# Pallette_v2.net
KiCad netlist of a schematic drawn in Altium Designer
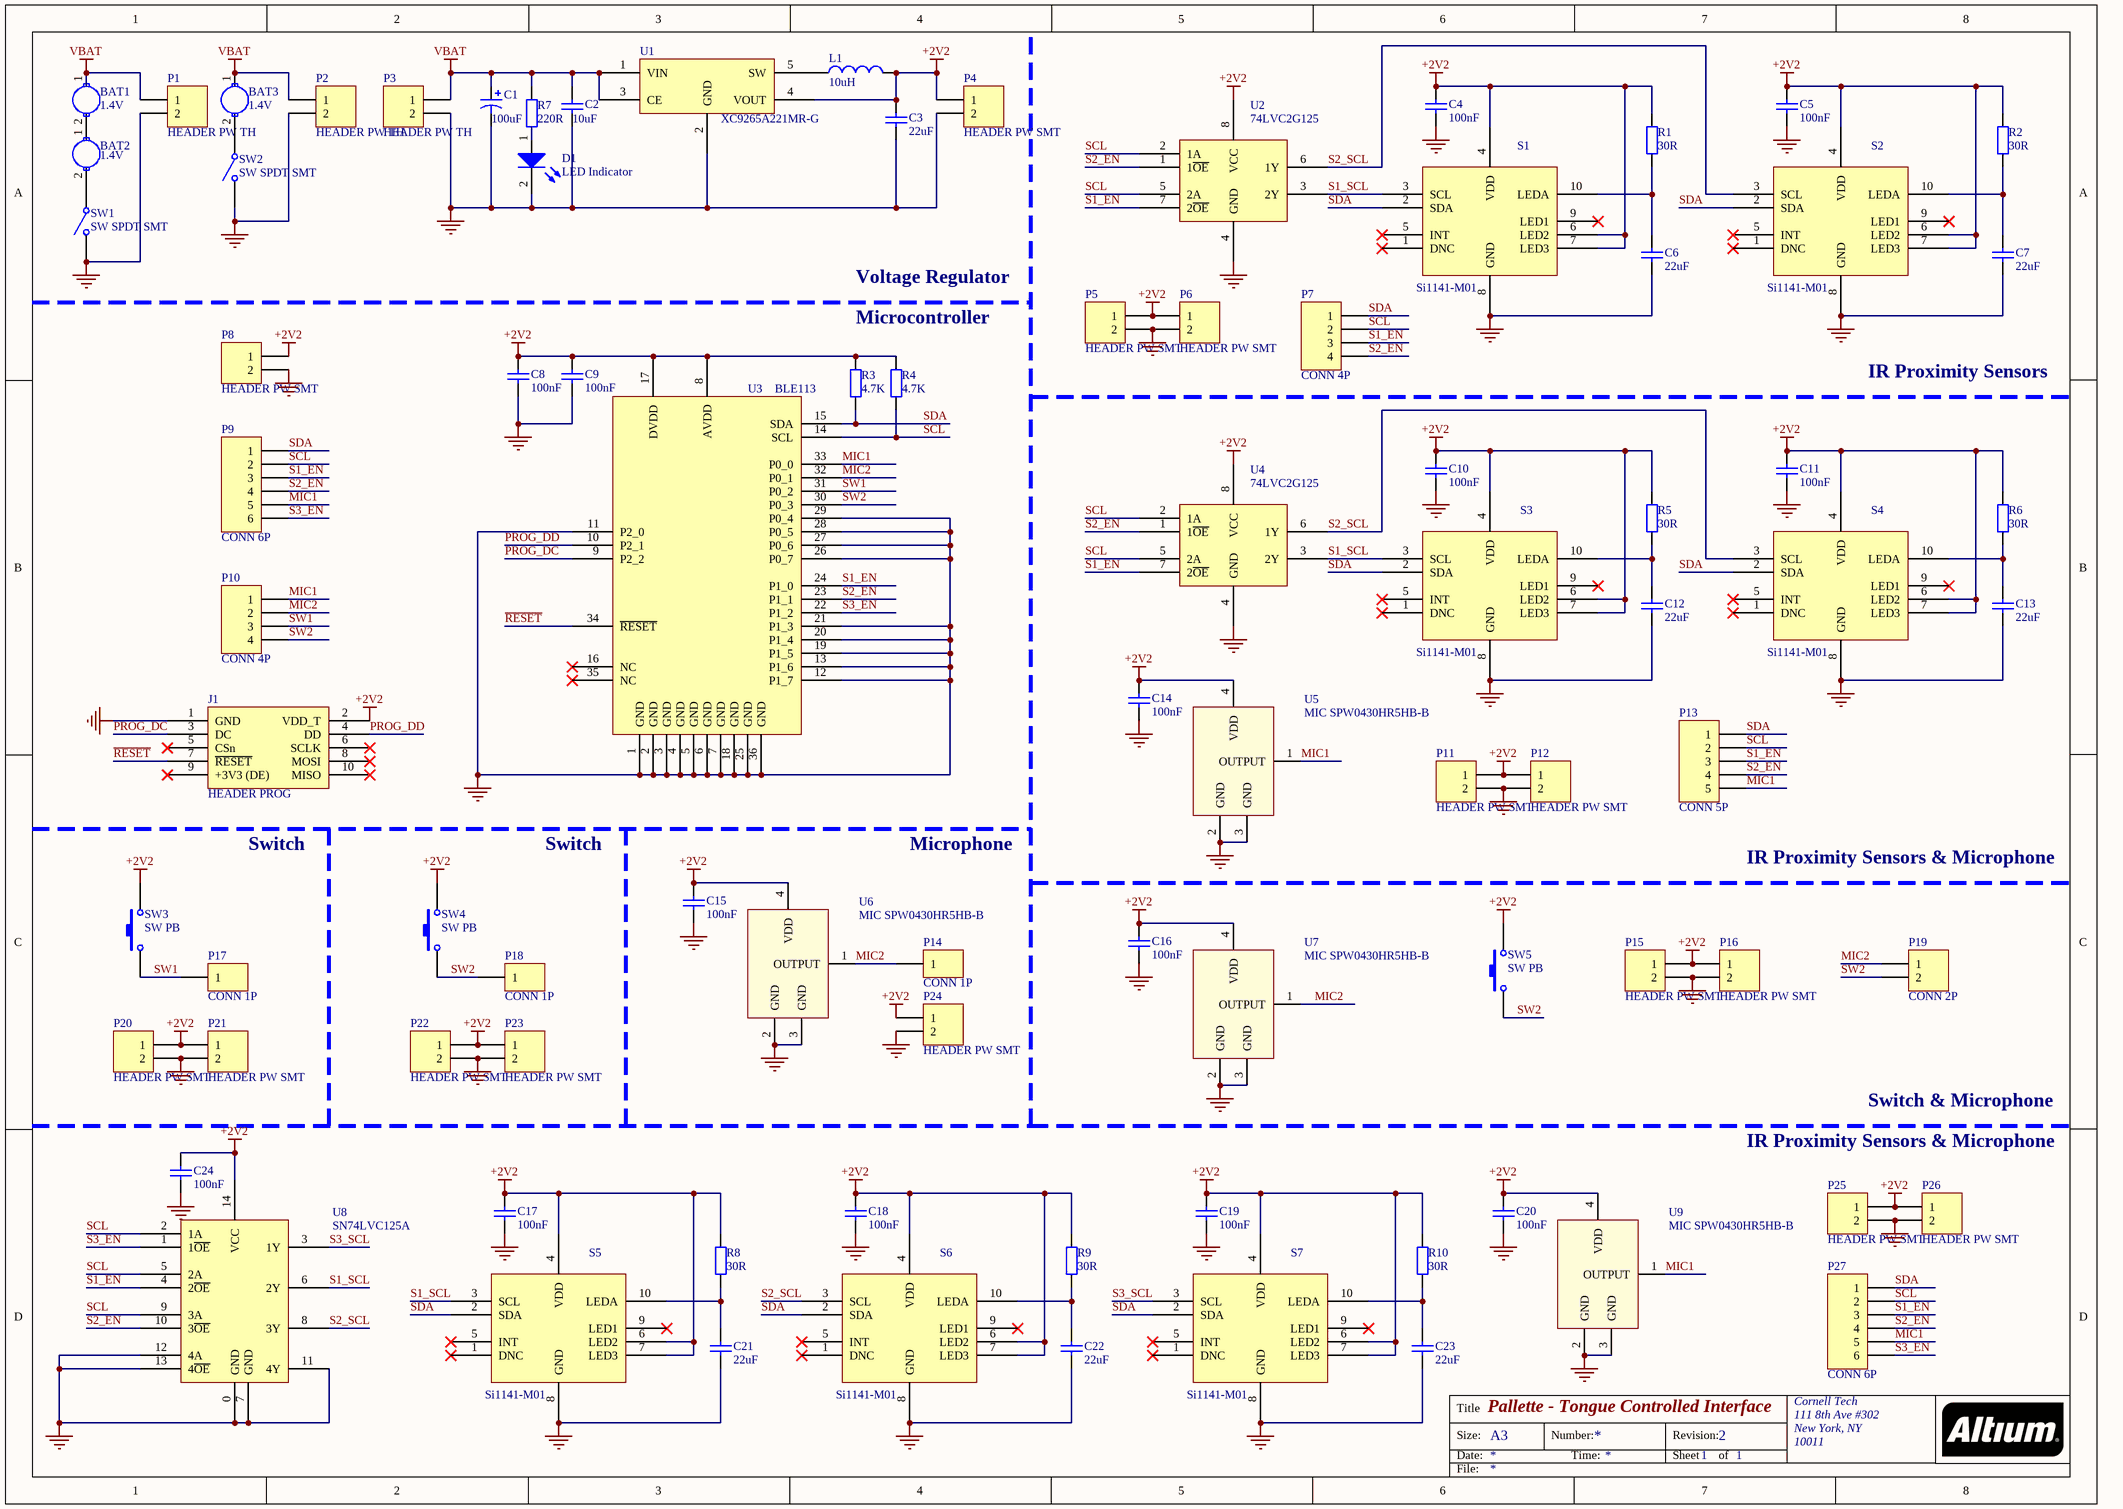
[diagram p0: Pallette v2.SchDoc]

(export (version "E")
  (design (tool "Eeschema 10.0.6"))
  (components
    (comp (ref "BAT1")
      (value "1.4V")
      (footprint "BAT RETAINER 13")
      (description "RETAINER COIN CELL SMD 7.9MM")
      (fields
        (field (name "DIGI-KEY PART NUMBER") "36-2988-ND")
        (field (name "MANUFACTURER") "Keystone Electronics")
      )
      (libsource (lib "Schlib") (part "BAT RETAINER 13"))
    )
    (comp (ref "BAT2")
      (value "1.4V")
      (footprint "BAT RETAINER 13")
      (description "RETAINER COIN CELL SMD 7.9MM")
      (fields
        (field (name "DIGI-KEY PART NUMBER") "36-2988-ND")
        (field (name "MANUFACTURER") "Keystone Electronics")
      )
      (libsource (lib "Schlib") (part "BAT RETAINER 13"))
    )
    (comp (ref "BAT3")
      (value "1.4V")
      (footprint "BAT RETAINER 13")
      (description "RETAINER COIN CELL SMD 7.9MM")
      (fields
        (field (name "DIGI-KEY PART NUMBER") "36-2988-ND")
        (field (name "MANUFACTURER") "Keystone Electronics")
      )
      (libsource (lib "Schlib") (part "BAT RETAINER 13"))
    )
    (comp (ref "C1")
      (value "100uF")
      (footprint "1411")
      (description "CAP TANT POLY 100UF 8V 1411")
      (fields
        (field (name "DIGI-KEY PART NUMBER") "P16641CT-ND")
        (field (name "MANUFACTURER") "Panasonic Electronic Components")
      )
      (libsource (lib "Schlib") (part "CAP Pol 100uF"))
    )
    (comp (ref "C2")
      (value "10uF")
      (footprint "0603")
      (description "CAP CER 10UF ±20% 10V X5R 0603")
      (fields
        (field (name "DIGI-KEY PART NUMBER") "490-12734-1-ND")
        (field (name "MANUFACTURER PART NUMBER") "GRM188R61A106MAALD")
      )
      (libsource (lib "Schlib") (part "CAP 10uF"))
    )
    (comp (ref "C3")
      (value "22uF")
      (footprint "0603")
      (description "CAP CER 22UF 6.3V X5R 0603")
      (fields
        (field (name "DIGI-KEY PART NUMBER") "490-7611-1-ND")
        (field (name "MANUFACTURER PART NUMBER") "GRM188R60J226MEA0D")
      )
      (libsource (lib "Schlib") (part "CAP 22uF"))
    )
    (comp (ref "C4")
      (value "100nF")
      (footprint "0402")
      (description "CAP CER 0.1UF 10V X5R 0402")
      (fields (field (name "DIGI-KEY PART NUMBER") "490-1318-1-ND") (field (name "MANUFACTURER") "Murata"))
      (libsource (lib "Schlib") (part "CAP 100nF"))
    )
    (comp (ref "C5")
      (value "100nF")
      (footprint "0402")
      (description "CAP CER 0.1UF 10V X5R 0402")
      (fields (field (name "DIGI-KEY PART NUMBER") "490-1318-1-ND") (field (name "MANUFACTURER") "Murata"))
      (libsource (lib "Schlib") (part "CAP 100nF"))
    )
    (comp (ref "C6")
      (value "22uF")
      (footprint "0603")
      (description "CAP CER 22UF 6.3V X5R 0603")
      (fields
        (field (name "DIGI-KEY PART NUMBER") "490-7611-1-ND")
        (field (name "MANUFACTURER PART NUMBER") "GRM188R60J226MEA0D")
      )
      (libsource (lib "Schlib") (part "CAP 22uF"))
    )
    (comp (ref "C7")
      (value "22uF")
      (footprint "0603")
      (description "CAP CER 22UF 6.3V X5R 0603")
      (fields
        (field (name "DIGI-KEY PART NUMBER") "490-7611-1-ND")
        (field (name "MANUFACTURER PART NUMBER") "GRM188R60J226MEA0D")
      )
      (libsource (lib "Schlib") (part "CAP 22uF"))
    )
    (comp (ref "C8")
      (value "100nF")
      (footprint "0402")
      (description "CAP CER 0.1UF 10V X5R 0402")
      (fields (field (name "DIGI-KEY PART NUMBER") "490-1318-1-ND") (field (name "MANUFACTURER") "Murata"))
      (libsource (lib "Schlib") (part "CAP 100nF"))
    )
    (comp (ref "C9")
      (value "100nF")
      (footprint "0402")
      (description "CAP CER 0.1UF 10V X5R 0402")
      (fields (field (name "DIGI-KEY PART NUMBER") "490-1318-1-ND") (field (name "MANUFACTURER") "Murata"))
      (libsource (lib "Schlib") (part "CAP 100nF"))
    )
    (comp (ref "C10")
      (value "100nF")
      (footprint "0402")
      (description "CAP CER 0.1UF 10V X5R 0402")
      (fields (field (name "DIGI-KEY PART NUMBER") "490-1318-1-ND") (field (name "MANUFACTURER") "Murata"))
      (libsource (lib "Schlib") (part "CAP 100nF"))
    )
    (comp (ref "C11")
      (value "100nF")
      (footprint "0402")
      (description "CAP CER 0.1UF 10V X5R 0402")
      (fields (field (name "DIGI-KEY PART NUMBER") "490-1318-1-ND") (field (name "MANUFACTURER") "Murata"))
      (libsource (lib "Schlib") (part "CAP 100nF"))
    )
    (comp (ref "C12")
      (value "22uF")
      (footprint "0603")
      (description "CAP CER 22UF 6.3V X5R 0603")
      (fields
        (field (name "DIGI-KEY PART NUMBER") "490-7611-1-ND")
        (field (name "MANUFACTURER PART NUMBER") "GRM188R60J226MEA0D")
      )
      (libsource (lib "Schlib") (part "CAP 22uF"))
    )
    (comp (ref "C13")
      (value "22uF")
      (footprint "0603")
      (description "CAP CER 22UF 6.3V X5R 0603")
      (fields
        (field (name "DIGI-KEY PART NUMBER") "490-7611-1-ND")
        (field (name "MANUFACTURER PART NUMBER") "GRM188R60J226MEA0D")
      )
      (libsource (lib "Schlib") (part "CAP 22uF"))
    )
    (comp (ref "C14")
      (value "100nF")
      (footprint "0402")
      (description "CAP CER 0.1UF 10V X5R 0402")
      (fields (field (name "DIGI-KEY PART NUMBER") "490-1318-1-ND") (field (name "MANUFACTURER") "Murata"))
      (libsource (lib "Schlib") (part "CAP 100nF"))
    )
    (comp (ref "C15")
      (value "100nF")
      (footprint "0402")
      (description "CAP CER 0.1UF 10V X5R 0402")
      (fields (field (name "DIGI-KEY PART NUMBER") "490-1318-1-ND") (field (name "MANUFACTURER") "Murata"))
      (libsource (lib "Schlib") (part "CAP 100nF"))
    )
    (comp (ref "C16")
      (value "100nF")
      (footprint "0402")
      (description "CAP CER 0.1UF 10V X5R 0402")
      (fields (field (name "DIGI-KEY PART NUMBER") "490-1318-1-ND") (field (name "MANUFACTURER") "Murata"))
      (libsource (lib "Schlib") (part "CAP 100nF"))
    )
    (comp (ref "C17")
      (value "100nF")
      (footprint "0402")
      (description "CAP CER 0.1UF 10V X5R 0402")
      (fields (field (name "DIGI-KEY PART NUMBER") "490-1318-1-ND") (field (name "MANUFACTURER") "Murata"))
      (libsource (lib "Schlib") (part "CAP 100nF"))
    )
    (comp (ref "C18")
      (value "100nF")
      (footprint "0402")
      (description "CAP CER 0.1UF 10V X5R 0402")
      (fields (field (name "DIGI-KEY PART NUMBER") "490-1318-1-ND") (field (name "MANUFACTURER") "Murata"))
      (libsource (lib "Schlib") (part "CAP 100nF"))
    )
    (comp (ref "C19")
      (value "100nF")
      (footprint "0402")
      (description "CAP CER 0.1UF 10V X5R 0402")
      (fields (field (name "DIGI-KEY PART NUMBER") "490-1318-1-ND") (field (name "MANUFACTURER") "Murata"))
      (libsource (lib "Schlib") (part "CAP 100nF"))
    )
    (comp (ref "C20")
      (value "100nF")
      (footprint "0402")
      (description "CAP CER 0.1UF 10V X5R 0402")
      (fields (field (name "DIGI-KEY PART NUMBER") "490-1318-1-ND") (field (name "MANUFACTURER") "Murata"))
      (libsource (lib "Schlib") (part "CAP 100nF"))
    )
    (comp (ref "C21")
      (value "22uF")
      (footprint "0603")
      (description "CAP CER 22UF 6.3V X5R 0603")
      (fields
        (field (name "DIGI-KEY PART NUMBER") "490-7611-1-ND")
        (field (name "MANUFACTURER PART NUMBER") "GRM188R60J226MEA0D")
      )
      (libsource (lib "Schlib") (part "CAP 22uF"))
    )
    (comp (ref "C22")
      (value "22uF")
      (footprint "0603")
      (description "CAP CER 22UF 6.3V X5R 0603")
      (fields
        (field (name "DIGI-KEY PART NUMBER") "490-7611-1-ND")
        (field (name "MANUFACTURER PART NUMBER") "GRM188R60J226MEA0D")
      )
      (libsource (lib "Schlib") (part "CAP 22uF"))
    )
    (comp (ref "C23")
      (value "22uF")
      (footprint "0603")
      (description "CAP CER 22UF 6.3V X5R 0603")
      (fields
        (field (name "DIGI-KEY PART NUMBER") "490-7611-1-ND")
        (field (name "MANUFACTURER PART NUMBER") "GRM188R60J226MEA0D")
      )
      (libsource (lib "Schlib") (part "CAP 22uF"))
    )
    (comp (ref "C24")
      (value "100nF")
      (footprint "0402")
      (description "CAP CER 0.1UF 10V X5R 0402")
      (fields (field (name "DIGI-KEY PART NUMBER") "490-1318-1-ND") (field (name "MANUFACTURER") "Murata"))
      (libsource (lib "Schlib") (part "CAP 100nF"))
    )
    (comp (ref "D1")
      (value "LED Indicator")
      (footprint "LED")
      (description "LED Red 630nm 2.2V Diffused White Lens 0603")
      (fields
        (field (name "DIGIKEY PART NUMBER") "SML-D12V1WT86CT-ND")
        (field (name "MANUFACTURER PART NUMBER") "SML-D12V1WT86")
      )
      (libsource (lib "Schlib") (part "LED Indicator"))
    )
    (comp (ref "J1")
      (value "HEADER PROG")
      (footprint "TC2050-IDC-NL")
      (description "PADS PROGRAMMING")
      (libsource (lib "Schlib") (part "HEADER PROG"))
    )
    (comp (ref "L1")
      (value "10uH")
      (footprint "0805")
      (description "FIXED IND 10UH 500MA 320 MOHM")
      (fields
        (field (name "DIGI-KEY PART NUMBER") "535-12791-1-ND")
        (field (name "MANUFACTURER") "Abracon LLC")
      )
      (libsource (lib "Schlib") (part "IND 10uH"))
    )
    (comp (ref "P1")
      (value "HEADER PW TH")
      (footprint "PORT PW TH 2P")
      (description "PADS POWER")
      (fields (field (name "PUBLISHER") "Altium Limited"))
      (libsource (lib "Schlib") (part "HEADER PW TH"))
    )
    (comp (ref "P2")
      (value "HEADER PW TH")
      (footprint "PORT PW TH 2P")
      (description "PADS POWER")
      (fields (field (name "PUBLISHER") "Altium Limited"))
      (libsource (lib "Schlib") (part "HEADER PW TH"))
    )
    (comp (ref "P3")
      (value "HEADER PW TH")
      (footprint "PORT PW TH 2P")
      (description "PADS POWER")
      (fields (field (name "PUBLISHER") "Altium Limited"))
      (libsource (lib "") (part "HEADER PW TH_1"))
    )
    (comp (ref "P4")
      (value "HEADER PW SMT")
      (footprint "PORT PW SMT 2P")
      (description "Connection Port")
      (fields (field (name "PUBLISHER") "Altium Limited"))
      (libsource (lib "Schlib") (part "HEADER PW SMT"))
    )
    (comp (ref "P5")
      (value "HEADER PW SMT")
      (footprint "PORT PW SMT 2P")
      (description "Connection Port")
      (fields (field (name "PUBLISHER") "Altium Limited"))
      (libsource (lib "") (part "HEADER PW SMT_1"))
    )
    (comp (ref "P6")
      (value "HEADER PW SMT")
      (footprint "PORT PW SMT 2P")
      (description "Connection Port")
      (fields (field (name "PUBLISHER") "Altium Limited"))
      (libsource (lib "Schlib") (part "HEADER PW SMT"))
    )
    (comp (ref "P7")
      (value "CONN 4P")
      (footprint "PORT CONN 4P")
      (description "Connection Port")
      (fields (field (name "PUBLISHER") "Altium Limited"))
      (libsource (lib "Schlib") (part "HEADER CONN 4P"))
    )
    (comp (ref "P8")
      (value "HEADER PW SMT")
      (footprint "PORT PW SMT 2P")
      (description "Connection Port")
      (fields (field (name "PUBLISHER") "Altium Limited"))
      (libsource (lib "") (part "HEADER PW SMT_1"))
    )
    (comp (ref "P9")
      (value "CONN 6P")
      (footprint "PORT CONN 6P")
      (description "Connection Port")
      (fields (field (name "PUBLISHER") "Altium Limited"))
      (libsource (lib "Schlib") (part "HEADER CONN 6P"))
    )
    (comp (ref "P10")
      (value "CONN 4P")
      (footprint "PORT CONN 4P")
      (description "Connection Port")
      (fields (field (name "PUBLISHER") "Altium Limited"))
      (libsource (lib "Schlib") (part "HEADER CONN 4P"))
    )
    (comp (ref "P11")
      (value "HEADER PW SMT")
      (footprint "PORT PW SMT 2P")
      (description "Connection Port")
      (fields (field (name "PUBLISHER") "Altium Limited"))
      (libsource (lib "") (part "HEADER PW SMT_1"))
    )
    (comp (ref "P12")
      (value "HEADER PW SMT")
      (footprint "PORT PW SMT 2P")
      (description "Connection Port")
      (fields (field (name "PUBLISHER") "Altium Limited"))
      (libsource (lib "Schlib") (part "HEADER PW SMT"))
    )
    (comp (ref "P13")
      (value "CONN 5P")
      (footprint "PORT CONN 5P")
      (description "Connection Port")
      (libsource (lib "Schlib") (part "HEADER CONN 5P"))
    )
    (comp (ref "P14")
      (value "CONN 1P")
      (footprint "PORT CONN 1P")
      (description "Connection Port")
      (libsource (lib "Schlib") (part "HEADER CONN 1P"))
    )
    (comp (ref "P15")
      (value "HEADER PW SMT")
      (footprint "PORT PW SMT 2P")
      (description "Connection Port")
      (fields (field (name "PUBLISHER") "Altium Limited"))
      (libsource (lib "") (part "HEADER PW SMT_1"))
    )
    (comp (ref "P16")
      (value "HEADER PW SMT")
      (footprint "PORT PW SMT 2P")
      (description "Connection Port")
      (fields (field (name "PUBLISHER") "Altium Limited"))
      (libsource (lib "Schlib") (part "HEADER PW SMT"))
    )
    (comp (ref "P17")
      (value "CONN 1P")
      (footprint "PORT CONN 1P")
      (description "Connection Port")
      (libsource (lib "Schlib") (part "HEADER CONN 1P"))
    )
    (comp (ref "P18")
      (value "CONN 1P")
      (footprint "PORT CONN 1P")
      (description "Connection Port")
      (libsource (lib "Schlib") (part "HEADER CONN 1P"))
    )
    (comp (ref "P19")
      (value "CONN 2P")
      (footprint "PORT CONN 2P")
      (description "Connection Port")
      (fields (field (name "PUBLISHER") "Altium Limited"))
      (libsource (lib "Schlib") (part "HEADER CONN 2P"))
    )
    (comp (ref "P20")
      (value "HEADER PW SMT")
      (footprint "PORT PW SMT 2P")
      (description "Connection Port")
      (fields (field (name "PUBLISHER") "Altium Limited"))
      (libsource (lib "") (part "HEADER PW SMT_1"))
    )
    (comp (ref "P21")
      (value "HEADER PW SMT")
      (footprint "PORT PW SMT 2P")
      (description "Connection Port")
      (fields (field (name "PUBLISHER") "Altium Limited"))
      (libsource (lib "Schlib") (part "HEADER PW SMT"))
    )
    (comp (ref "P22")
      (value "HEADER PW SMT")
      (footprint "PORT PW SMT 2P")
      (description "Connection Port")
      (fields (field (name "PUBLISHER") "Altium Limited"))
      (libsource (lib "") (part "HEADER PW SMT_1"))
    )
    (comp (ref "P23")
      (value "HEADER PW SMT")
      (footprint "PORT PW SMT 2P")
      (description "Connection Port")
      (fields (field (name "PUBLISHER") "Altium Limited"))
      (libsource (lib "Schlib") (part "HEADER PW SMT"))
    )
    (comp (ref "P24")
      (value "HEADER PW SMT")
      (footprint "PORT PW SMT 2P")
      (description "Connection Port")
      (fields (field (name "PUBLISHER") "Altium Limited"))
      (libsource (lib "Schlib") (part "HEADER PW SMT"))
    )
    (comp (ref "P25")
      (value "HEADER PW SMT")
      (footprint "PORT PW SMT 2P")
      (description "Connection Port")
      (fields (field (name "PUBLISHER") "Altium Limited"))
      (libsource (lib "") (part "HEADER PW SMT_1"))
    )
    (comp (ref "P26")
      (value "HEADER PW SMT")
      (footprint "PORT PW SMT 2P")
      (description "Connection Port")
      (fields (field (name "PUBLISHER") "Altium Limited"))
      (libsource (lib "Schlib") (part "HEADER PW SMT"))
    )
    (comp (ref "P27")
      (value "CONN 6P")
      (footprint "PORT CONN 6P")
      (description "Connection Port")
      (fields (field (name "PUBLISHER") "Altium Limited"))
      (libsource (lib "Schlib") (part "HEADER CONN 6P"))
    )
    (comp (ref "R1")
      (value "30R")
      (footprint "0402")
      (description "RES SMD 30 OHM 1% 1/16W 0402")
      (fields (field (name "DIGI-KEY PART NUMBER") "311-30LRCT-ND") (field (name "MANUFACTURER") "Yageo"))
      (libsource (lib "Schlib") (part "RES 30R"))
    )
    (comp (ref "R2")
      (value "30R")
      (footprint "0402")
      (description "RES SMD 30 OHM 1% 1/16W 0402")
      (fields (field (name "DIGI-KEY PART NUMBER") "311-30LRCT-ND") (field (name "MANUFACTURER") "Yageo"))
      (libsource (lib "Schlib") (part "RES 30R"))
    )
    (comp (ref "R3")
      (value "4.7K")
      (footprint "0402")
      (description "RES SMD 4.7K OHM 1% 1/16W 0402")
      (fields (field (name "DIGI-KEY PART NUMBER") "311-4.7KLRCT-ND") (field (name "MANUFACTURER") "Yageo"))
      (libsource (lib "Schlib") (part "RES 4.7K"))
    )
    (comp (ref "R4")
      (value "4.7K")
      (footprint "0402")
      (description "RES SMD 4.7K OHM 1% 1/16W 0402")
      (fields (field (name "DIGI-KEY PART NUMBER") "311-4.7KLRCT-ND") (field (name "MANUFACTURER") "Yageo"))
      (libsource (lib "Schlib") (part "RES 4.7K"))
    )
    (comp (ref "R5")
      (value "30R")
      (footprint "0402")
      (description "RES SMD 30 OHM 1% 1/16W 0402")
      (fields (field (name "DIGI-KEY PART NUMBER") "311-30LRCT-ND") (field (name "MANUFACTURER") "Yageo"))
      (libsource (lib "Schlib") (part "RES 30R"))
    )
    (comp (ref "R6")
      (value "30R")
      (footprint "0402")
      (description "RES SMD 30 OHM 1% 1/16W 0402")
      (fields (field (name "DIGI-KEY PART NUMBER") "311-30LRCT-ND") (field (name "MANUFACTURER") "Yageo"))
      (libsource (lib "Schlib") (part "RES 30R"))
    )
    (comp (ref "R7")
      (value "220R")
      (footprint "0603")
      (description "RES SMD 220 OHM 1% 1/10W 0603")
      (fields (field (name "DIGI-KEY PART NUMBER") "P220HCT-ND") (field (name "MANUFACTURER") "Panasonic"))
      (libsource (lib "Schlib") (part "RES 220R"))
    )
    (comp (ref "R8")
      (value "30R")
      (footprint "0402")
      (description "RES SMD 30 OHM 1% 1/16W 0402")
      (fields (field (name "DIGI-KEY PART NUMBER") "311-30LRCT-ND") (field (name "MANUFACTURER") "Yageo"))
      (libsource (lib "Schlib") (part "RES 30R"))
    )
    (comp (ref "R9")
      (value "30R")
      (footprint "0402")
      (description "RES SMD 30 OHM 1% 1/16W 0402")
      (fields (field (name "DIGI-KEY PART NUMBER") "311-30LRCT-ND") (field (name "MANUFACTURER") "Yageo"))
      (libsource (lib "Schlib") (part "RES 30R"))
    )
    (comp (ref "R10")
      (value "30R")
      (footprint "0402")
      (description "RES SMD 30 OHM 1% 1/16W 0402")
      (fields (field (name "DIGI-KEY PART NUMBER") "311-30LRCT-ND") (field (name "MANUFACTURER") "Yageo"))
      (libsource (lib "Schlib") (part "RES 30R"))
    )
    (comp (ref "S1")
      (value "Si1141-M01")
      (footprint "SI1141-M01")
      (description "SENS IR PROXIMITY AMB LT 10QFN")
      (fields
        (field (name "DIGI-KEY PART NUMBER") "336-3260-1-ND")
        (field (name "MANUFACTURER") "Silicon Labs")
      )
      (libsource (lib "Schlib") (part "Si1141-M01"))
    )
    (comp (ref "S2")
      (value "Si1141-M01")
      (footprint "SI1141-M01")
      (description "SENS IR PROXIMITY AMB LT 10QFN")
      (fields
        (field (name "DIGI-KEY PART NUMBER") "336-3260-1-ND")
        (field (name "MANUFACTURER") "Silicon Labs")
      )
      (libsource (lib "Schlib") (part "Si1141-M01"))
    )
    (comp (ref "S3")
      (value "Si1141-M01")
      (footprint "SI1141-M01")
      (description "SENS IR PROXIMITY AMB LT 10QFN")
      (fields
        (field (name "DIGI-KEY PART NUMBER") "336-3260-1-ND")
        (field (name "MANUFACTURER") "Silicon Labs")
      )
      (libsource (lib "Schlib") (part "Si1141-M01"))
    )
    (comp (ref "S4")
      (value "Si1141-M01")
      (footprint "SI1141-M01")
      (description "SENS IR PROXIMITY AMB LT 10QFN")
      (fields
        (field (name "DIGI-KEY PART NUMBER") "336-3260-1-ND")
        (field (name "MANUFACTURER") "Silicon Labs")
      )
      (libsource (lib "Schlib") (part "Si1141-M01"))
    )
    (comp (ref "S5")
      (value "Si1141-M01")
      (footprint "SI1141-M01")
      (description "SENS IR PROXIMITY AMB LT 10QFN")
      (fields
        (field (name "DIGI-KEY PART NUMBER") "336-3260-1-ND")
        (field (name "MANUFACTURER") "Silicon Labs")
      )
      (libsource (lib "Schlib") (part "Si1141-M01"))
    )
    (comp (ref "S6")
      (value "Si1141-M01")
      (footprint "SI1141-M01")
      (description "SENS IR PROXIMITY AMB LT 10QFN")
      (fields
        (field (name "DIGI-KEY PART NUMBER") "336-3260-1-ND")
        (field (name "MANUFACTURER") "Silicon Labs")
      )
      (libsource (lib "Schlib") (part "Si1141-M01"))
    )
    (comp (ref "S7")
      (value "Si1141-M01")
      (footprint "SI1141-M01")
      (description "SENS IR PROXIMITY AMB LT 10QFN")
      (fields
        (field (name "DIGI-KEY PART NUMBER") "336-3260-1-ND")
        (field (name "MANUFACTURER") "Silicon Labs")
      )
      (libsource (lib "Schlib") (part "Si1141-M01"))
    )
    (comp (ref "SW1")
      (value "SW SPDT SMT")
      (footprint "SW SPDT SMT")
      (description "SW Single-Pole Double-Throw SMT Right-Angle")
      (fields
        (field (name "DIGIKEY PART NUMBER") "401-2000-ND")
        (field (name "MANUFACTURER") "C&K Components")
      )
      (libsource (lib "Schlib") (part "SW SPDT SMT"))
    )
    (comp (ref "SW2")
      (value "SW SPDT SMT")
      (footprint "SW SPDT SMT")
      (description "SW Single-Pole Double-Throw SMT Right-Angle")
      (fields
        (field (name "DIGIKEY PART NUMBER") "401-2000-ND")
        (field (name "MANUFACTURER") "C&K Components")
      )
      (libsource (lib "Schlib") (part "SW SPDT SMT"))
    )
    (comp (ref "SW3")
      (value "SW PB")
      (footprint "SW PB")
      (description "Switch Button")
      (libsource (lib "Schlib") (part "SW PB"))
    )
    (comp (ref "SW4")
      (value "SW PB")
      (footprint "SW PB")
      (description "Switch Button")
      (libsource (lib "Schlib") (part "SW PB"))
    )
    (comp (ref "SW5")
      (value "SW PB")
      (footprint "SW PB")
      (description "Switch Button")
      (libsource (lib "Schlib") (part "SW PB"))
    )
    (comp (ref "U1")
      (value "XC9265A221MR-G")
      (footprint "SOT-25")
      (description "IC REG BUCK 2.2V 0.2A SYNC SOT25")
      (fields
        (field (name "DIGI-KEY PART NUMBER") "893-1305-1-ND")
        (field (name "MANUFACTURER") "Torex Semiconductor Ltd")
      )
      (libsource (lib "Schlib") (part "VR XC9265A221MR-G"))
    )
    (comp (ref "U2")
      (value "74LVC2G125")
      (footprint "VSSOP8")
      (description "IC BUS BUFF DVR TRI-ST DL 8VSSOP")
      (fields
        (field (name "MANUFACTURER") "NXP Semiconductors")
        (field (name "MANUFACTURER PART NUMBER") "74LVC2G125DC,125")
      )
      (libsource (lib "Schlib") (part "BUFF 74LVC2G125"))
    )
    (comp (ref "U3")
      (value "BLE113")
      (footprint "BLE113-A")
      (description "MODULE BT 4.0 BLE113 OTA")
      (fields
        (field (name "MANUFACTURER") "Silicon Labs")
        (field (name "MANUFACTURER PART NUMBER") "BLE113-A-M256K")
      )
      (libsource (lib "Schlib") (part "uC BLE113"))
    )
    (comp (ref "U4")
      (value "74LVC2G125")
      (footprint "VSSOP8")
      (description "IC BUS BUFF DVR TRI-ST DL 8VSSOP")
      (fields
        (field (name "MANUFACTURER") "NXP Semiconductors")
        (field (name "MANUFACTURER PART NUMBER") "74LVC2G125DC,125")
      )
      (libsource (lib "Schlib") (part "BUFF 74LVC2G125"))
    )
    (comp (ref "U5")
      (value "MIC SPW0430HR5HB-B")
      (footprint "MIC-4P")
      (description "MIC MEMS ANALOG OMNI")
      (fields (field (name "DIGI-KEY PART NUMBER") "423-1215-1-ND") (field (name "MANUFACTURER") "Knowles"))
      (libsource (lib "Schlib") (part "MIC SPW0430HR5HB-B"))
    )
    (comp (ref "U6")
      (value "MIC SPW0430HR5HB-B")
      (footprint "MIC-4P")
      (description "MIC MEMS ANALOG OMNI")
      (fields (field (name "DIGI-KEY PART NUMBER") "423-1215-1-ND") (field (name "MANUFACTURER") "Knowles"))
      (libsource (lib "Schlib") (part "MIC SPW0430HR5HB-B"))
    )
    (comp (ref "U7")
      (value "MIC SPW0430HR5HB-B")
      (footprint "MIC-4P")
      (description "MIC MEMS ANALOG OMNI")
      (fields (field (name "DIGI-KEY PART NUMBER") "423-1215-1-ND") (field (name "MANUFACTURER") "Knowles"))
      (libsource (lib "Schlib") (part "MIC SPW0430HR5HB-B"))
    )
    (comp (ref "U8")
      (value "SN74LVC125A")
      (footprint "VQFN14")
      (description "IC BUS BUFF TRI-ST QD 14VQFN")
      (fields
        (field (name "MANUFACTURER") "Texas Instruments")
        (field (name "MANUFACTURER PART NUMBER") "SN74LVC125ARGYR")
      )
      (libsource (lib "Schlib") (part "BUFF SN74LVC125A"))
    )
    (comp (ref "U9")
      (value "MIC SPW0430HR5HB-B")
      (footprint "MIC-4P")
      (description "MIC MEMS ANALOG OMNI")
      (fields (field (name "DIGI-KEY PART NUMBER") "423-1215-1-ND") (field (name "MANUFACTURER") "Knowles"))
      (libsource (lib "Schlib") (part "MIC SPW0430HR5HB-B"))
    )
  )
  (nets
    (net (code "1") (name "+2V2") (class "Default")
      (node (ref "C10") (pin "2") (pinfunction "2_2") (pintype "passive"))
      (node (ref "C11") (pin "2") (pinfunction "2_2") (pintype "passive"))
      (node (ref "C14") (pin "1") (pinfunction "1_1") (pintype "passive"))
      (node (ref "C15") (pin "1") (pinfunction "1_1") (pintype "passive"))
      (node (ref "C16") (pin "1") (pinfunction "1_1") (pintype "passive"))
      (node (ref "C17") (pin "2") (pinfunction "2_2") (pintype "passive"))
      (node (ref "C18") (pin "2") (pinfunction "2_2") (pintype "passive"))
      (node (ref "C19") (pin "2") (pinfunction "2_2") (pintype "passive"))
      (node (ref "C20") (pin "1") (pinfunction "1_1") (pintype "passive"))
      (node (ref "C24") (pin "2") (pinfunction "2_2") (pintype "passive"))
      (node (ref "C3") (pin "2") (pinfunction "2_2") (pintype "passive"))
      (node (ref "C4") (pin "2") (pinfunction "2_2") (pintype "passive"))
      (node (ref "C5") (pin "2") (pinfunction "2_2") (pintype "passive"))
      (node (ref "C8") (pin "2") (pinfunction "2_2") (pintype "passive"))
      (node (ref "C9") (pin "2") (pinfunction "2_2") (pintype "passive"))
      (node (ref "J1") (pin "2") (pinfunction "VDD_T_2") (pintype "passive"))
      (node (ref "L1") (pin "2") (pinfunction "2_2") (pintype "passive"))
      (node (ref "P11") (pin "1") (pinfunction "1_1") (pintype "passive"))
      (node (ref "P12") (pin "1") (pinfunction "1_1") (pintype "passive"))
      (node (ref "P15") (pin "1") (pinfunction "1_1") (pintype "passive"))
      (node (ref "P16") (pin "1") (pinfunction "1_1") (pintype "passive"))
      (node (ref "P20") (pin "1") (pinfunction "1_1") (pintype "passive"))
      (node (ref "P21") (pin "1") (pinfunction "1_1") (pintype "passive"))
      (node (ref "P22") (pin "1") (pinfunction "1_1") (pintype "passive"))
      (node (ref "P23") (pin "1") (pinfunction "1_1") (pintype "passive"))
      (node (ref "P24") (pin "1") (pinfunction "1_1") (pintype "passive"))
      (node (ref "P25") (pin "1") (pinfunction "1_1") (pintype "passive"))
      (node (ref "P26") (pin "1") (pinfunction "1_1") (pintype "passive"))
      (node (ref "P4") (pin "1") (pinfunction "1_1") (pintype "passive"))
      (node (ref "P5") (pin "1") (pinfunction "1_1") (pintype "passive"))
      (node (ref "P6") (pin "1") (pinfunction "1_1") (pintype "passive"))
      (node (ref "P8") (pin "1") (pinfunction "1_1") (pintype "passive"))
      (node (ref "R1") (pin "2") (pinfunction "2_2") (pintype "passive"))
      (node (ref "R10") (pin "2") (pinfunction "2_2") (pintype "passive"))
      (node (ref "R2") (pin "2") (pinfunction "2_2") (pintype "passive"))
      (node (ref "R3") (pin "2") (pinfunction "2_2") (pintype "passive"))
      (node (ref "R4") (pin "2") (pinfunction "2_2") (pintype "passive"))
      (node (ref "R5") (pin "2") (pinfunction "2_2") (pintype "passive"))
      (node (ref "R6") (pin "2") (pinfunction "2_2") (pintype "passive"))
      (node (ref "R8") (pin "2") (pinfunction "2_2") (pintype "passive"))
      (node (ref "R9") (pin "2") (pinfunction "2_2") (pintype "passive"))
      (node (ref "S1") (pin "4") (pinfunction "VDD_4") (pintype "passive"))
      (node (ref "S1") (pin "6") (pinfunction "LED2_6") (pintype "passive"))
      (node (ref "S1") (pin "7") (pinfunction "LED3_7") (pintype "passive"))
      (node (ref "S2") (pin "4") (pinfunction "VDD_4") (pintype "passive"))
      (node (ref "S2") (pin "6") (pinfunction "LED2_6") (pintype "passive"))
      (node (ref "S2") (pin "7") (pinfunction "LED3_7") (pintype "passive"))
      (node (ref "S3") (pin "4") (pinfunction "VDD_4") (pintype "passive"))
      (node (ref "S3") (pin "6") (pinfunction "LED2_6") (pintype "passive"))
      (node (ref "S3") (pin "7") (pinfunction "LED3_7") (pintype "passive"))
      (node (ref "S4") (pin "4") (pinfunction "VDD_4") (pintype "passive"))
      (node (ref "S4") (pin "6") (pinfunction "LED2_6") (pintype "passive"))
      (node (ref "S4") (pin "7") (pinfunction "LED3_7") (pintype "passive"))
      (node (ref "S5") (pin "4") (pinfunction "VDD_4") (pintype "passive"))
      (node (ref "S5") (pin "6") (pinfunction "LED2_6") (pintype "passive"))
      (node (ref "S5") (pin "7") (pinfunction "LED3_7") (pintype "passive"))
      (node (ref "S6") (pin "4") (pinfunction "VDD_4") (pintype "passive"))
      (node (ref "S6") (pin "6") (pinfunction "LED2_6") (pintype "passive"))
      (node (ref "S6") (pin "7") (pinfunction "LED3_7") (pintype "passive"))
      (node (ref "S7") (pin "4") (pinfunction "VDD_4") (pintype "passive"))
      (node (ref "S7") (pin "6") (pinfunction "LED2_6") (pintype "passive"))
      (node (ref "S7") (pin "7") (pinfunction "LED3_7") (pintype "passive"))
      (node (ref "SW3") (pin "1") (pinfunction "1_1") (pintype "passive"))
      (node (ref "SW4") (pin "1") (pinfunction "1_1") (pintype "passive"))
      (node (ref "SW5") (pin "1") (pinfunction "1_1") (pintype "passive"))
      (node (ref "U1") (pin "4") (pinfunction "VOUT_4") (pintype "passive"))
      (node (ref "U2") (pin "8") (pinfunction "VCC_8") (pintype "passive"))
      (node (ref "U3") (pin "17") (pinfunction "DVDD_17") (pintype "passive"))
      (node (ref "U3") (pin "8") (pinfunction "AVDD_8") (pintype "passive"))
      (node (ref "U4") (pin "8") (pinfunction "VCC_8") (pintype "passive"))
      (node (ref "U5") (pin "4") (pinfunction "VDD_4") (pintype "passive"))
      (node (ref "U6") (pin "4") (pinfunction "VDD_4") (pintype "passive"))
      (node (ref "U7") (pin "4") (pinfunction "VDD_4") (pintype "passive"))
      (node (ref "U8") (pin "14") (pinfunction "VCC_14") (pintype "passive"))
      (node (ref "U9") (pin "4") (pinfunction "VDD_4") (pintype "passive"))
    )
    (net (code "2") (name "/MIC1") (class "Default")
      (node (ref "P10") (pin "1") (pinfunction "1_1") (pintype "passive"))
      (node (ref "P13") (pin "5") (pinfunction "5_5") (pintype "passive"))
      (node (ref "P27") (pin "5") (pinfunction "5_5") (pintype "passive"))
      (node (ref "P9") (pin "5") (pinfunction "5_5") (pintype "passive"))
      (node (ref "U3") (pin "33") (pinfunction "P0_0_33") (pintype "passive"))
      (node (ref "U5") (pin "1") (pinfunction "OUTPUT_1") (pintype "passive"))
      (node (ref "U9") (pin "1") (pinfunction "OUTPUT_1") (pintype "passive"))
    )
    (net (code "3") (name "/MIC2") (class "Default")
      (node (ref "P10") (pin "2") (pinfunction "2_2") (pintype "passive"))
      (node (ref "P14") (pin "1") (pinfunction "1_1") (pintype "passive"))
      (node (ref "P19") (pin "1") (pinfunction "1_1") (pintype "passive"))
      (node (ref "U3") (pin "32") (pinfunction "P0_1_32") (pintype "passive"))
      (node (ref "U6") (pin "1") (pinfunction "OUTPUT_1") (pintype "passive"))
      (node (ref "U7") (pin "1") (pinfunction "OUTPUT_1") (pintype "passive"))
    )
    (net (code "4") (name "/PROG_DC") (class "Default")
      (node (ref "J1") (pin "3") (pinfunction "DC_3") (pintype "passive"))
      (node (ref "U3") (pin "9") (pinfunction "P2_2_9") (pintype "passive"))
    )
    (net (code "5") (name "/PROG_DD") (class "Default")
      (node (ref "J1") (pin "4") (pinfunction "DD_4") (pintype "passive"))
      (node (ref "U3") (pin "10") (pinfunction "P2_1_10") (pintype "passive"))
    )
    (net (code "6") (name "/S1_EN") (class "Default")
      (node (ref "P13") (pin "3") (pinfunction "3_3") (pintype "passive"))
      (node (ref "P27") (pin "3") (pinfunction "3_3") (pintype "passive"))
      (node (ref "P7") (pin "3") (pinfunction "3_3") (pintype "passive"))
      (node (ref "P9") (pin "3") (pinfunction "3_3") (pintype "passive"))
      (node (ref "U2") (pin "7") (pinfunction "2~{OE}_7") (pintype "passive"))
      (node (ref "U3") (pin "24") (pinfunction "P1_0_24") (pintype "passive"))
      (node (ref "U4") (pin "7") (pinfunction "2~{OE}_7") (pintype "passive"))
      (node (ref "U8") (pin "4") (pinfunction "2~{OE}_4") (pintype "passive"))
    )
    (net (code "7") (name "/S1_SCL") (class "Default")
      (node (ref "S1") (pin "3") (pinfunction "SCL_3") (pintype "passive"))
      (node (ref "S3") (pin "3") (pinfunction "SCL_3") (pintype "passive"))
      (node (ref "S5") (pin "3") (pinfunction "SCL_3") (pintype "passive"))
      (node (ref "U2") (pin "3") (pinfunction "2Y_3") (pintype "passive"))
      (node (ref "U4") (pin "3") (pinfunction "2Y_3") (pintype "passive"))
      (node (ref "U8") (pin "6") (pinfunction "2Y_6") (pintype "passive"))
    )
    (net (code "8") (name "/S2_EN") (class "Default")
      (node (ref "P13") (pin "4") (pinfunction "4_4") (pintype "passive"))
      (node (ref "P27") (pin "4") (pinfunction "4_4") (pintype "passive"))
      (node (ref "P7") (pin "4") (pinfunction "4_4") (pintype "passive"))
      (node (ref "P9") (pin "4") (pinfunction "4_4") (pintype "passive"))
      (node (ref "U2") (pin "1") (pinfunction "1~{OE}_1") (pintype "passive"))
      (node (ref "U3") (pin "23") (pinfunction "P1_1_23") (pintype "passive"))
      (node (ref "U4") (pin "1") (pinfunction "1~{OE}_1") (pintype "passive"))
      (node (ref "U8") (pin "10") (pinfunction "3~{OE}_10") (pintype "passive"))
    )
    (net (code "9") (name "/S2_SCL") (class "Default")
      (node (ref "S2") (pin "3") (pinfunction "SCL_3") (pintype "passive"))
      (node (ref "S4") (pin "3") (pinfunction "SCL_3") (pintype "passive"))
      (node (ref "S6") (pin "3") (pinfunction "SCL_3") (pintype "passive"))
      (node (ref "U2") (pin "6") (pinfunction "1Y_6") (pintype "passive"))
      (node (ref "U4") (pin "6") (pinfunction "1Y_6") (pintype "passive"))
      (node (ref "U8") (pin "8") (pinfunction "3Y_8") (pintype "passive"))
    )
    (net (code "10") (name "/S3_EN") (class "Default")
      (node (ref "P27") (pin "6") (pinfunction "6_6") (pintype "passive"))
      (node (ref "P9") (pin "6") (pinfunction "6_6") (pintype "passive"))
      (node (ref "U3") (pin "22") (pinfunction "P1_2_22") (pintype "passive"))
      (node (ref "U8") (pin "1") (pinfunction "1~{OE}_1") (pintype "passive"))
    )
    (net (code "11") (name "/S3_SCL") (class "Default")
      (node (ref "S7") (pin "3") (pinfunction "SCL_3") (pintype "passive"))
      (node (ref "U8") (pin "3") (pinfunction "1Y_3") (pintype "passive"))
    )
    (net (code "12") (name "/SCL") (class "Default")
      (node (ref "P13") (pin "2") (pinfunction "2_2") (pintype "passive"))
      (node (ref "P27") (pin "2") (pinfunction "2_2") (pintype "passive"))
      (node (ref "P7") (pin "2") (pinfunction "2_2") (pintype "passive"))
      (node (ref "P9") (pin "2") (pinfunction "2_2") (pintype "passive"))
      (node (ref "R4") (pin "1") (pinfunction "1_1") (pintype "passive"))
      (node (ref "U2") (pin "2") (pinfunction "1A_2") (pintype "passive"))
      (node (ref "U2") (pin "5") (pinfunction "2A_5") (pintype "passive"))
      (node (ref "U3") (pin "14") (pinfunction "SCL_14") (pintype "passive"))
      (node (ref "U4") (pin "2") (pinfunction "1A_2") (pintype "passive"))
      (node (ref "U4") (pin "5") (pinfunction "2A_5") (pintype "passive"))
      (node (ref "U8") (pin "2") (pinfunction "1A_2") (pintype "passive"))
      (node (ref "U8") (pin "5") (pinfunction "2A_5") (pintype "passive"))
      (node (ref "U8") (pin "9") (pinfunction "3A_9") (pintype "passive"))
    )
    (net (code "13") (name "/SDA") (class "Default")
      (node (ref "P13") (pin "1") (pinfunction "1_1") (pintype "passive"))
      (node (ref "P27") (pin "1") (pinfunction "1_1") (pintype "passive"))
      (node (ref "P7") (pin "1") (pinfunction "1_1") (pintype "passive"))
      (node (ref "P9") (pin "1") (pinfunction "1_1") (pintype "passive"))
      (node (ref "R3") (pin "1") (pinfunction "1_1") (pintype "passive"))
      (node (ref "S1") (pin "2") (pinfunction "SDA_2") (pintype "passive"))
      (node (ref "S2") (pin "2") (pinfunction "SDA_2") (pintype "passive"))
      (node (ref "S3") (pin "2") (pinfunction "SDA_2") (pintype "passive"))
      (node (ref "S4") (pin "2") (pinfunction "SDA_2") (pintype "passive"))
      (node (ref "S5") (pin "2") (pinfunction "SDA_2") (pintype "passive"))
      (node (ref "S6") (pin "2") (pinfunction "SDA_2") (pintype "passive"))
      (node (ref "S7") (pin "2") (pinfunction "SDA_2") (pintype "passive"))
      (node (ref "U3") (pin "15") (pinfunction "SDA_15") (pintype "passive"))
    )
    (net (code "14") (name "/SW1") (class "Default")
      (node (ref "P10") (pin "3") (pinfunction "3_3") (pintype "passive"))
      (node (ref "P17") (pin "1") (pinfunction "1_1") (pintype "passive"))
      (node (ref "SW3") (pin "2") (pinfunction "2_2") (pintype "passive"))
      (node (ref "U3") (pin "31") (pinfunction "P0_2_31") (pintype "passive"))
    )
    (net (code "15") (name "/SW2") (class "Default")
      (node (ref "P10") (pin "4") (pinfunction "4_4") (pintype "passive"))
      (node (ref "P18") (pin "1") (pinfunction "1_1") (pintype "passive"))
      (node (ref "P19") (pin "2") (pinfunction "2_2") (pintype "passive"))
      (node (ref "SW4") (pin "2") (pinfunction "2_2") (pintype "passive"))
      (node (ref "SW5") (pin "2") (pinfunction "2_2") (pintype "passive"))
      (node (ref "U3") (pin "30") (pinfunction "P0_3_30") (pintype "passive"))
    )
    (net (code "16") (name "/~{RESET}") (class "Default")
      (node (ref "J1") (pin "7") (pinfunction "~{RESET}_7") (pintype "passive"))
      (node (ref "U3") (pin "34") (pinfunction "~{RESET}_34") (pintype "passive"))
    )
    (net (code "17") (name "GND") (class "Default")
      (node (ref "C1") (pin "2") (pinfunction "2_2") (pintype "passive"))
      (node (ref "C10") (pin "1") (pinfunction "1_1") (pintype "passive"))
      (node (ref "C11") (pin "1") (pinfunction "1_1") (pintype "passive"))
      (node (ref "C12") (pin "1") (pinfunction "1_1") (pintype "passive"))
      (node (ref "C13") (pin "1") (pinfunction "1_1") (pintype "passive"))
      (node (ref "C14") (pin "2") (pinfunction "2_2") (pintype "passive"))
      (node (ref "C15") (pin "2") (pinfunction "2_2") (pintype "passive"))
      (node (ref "C16") (pin "2") (pinfunction "2_2") (pintype "passive"))
      (node (ref "C17") (pin "1") (pinfunction "1_1") (pintype "passive"))
      (node (ref "C18") (pin "1") (pinfunction "1_1") (pintype "passive"))
      (node (ref "C19") (pin "1") (pinfunction "1_1") (pintype "passive"))
      (node (ref "C2") (pin "1") (pinfunction "1_1") (pintype "passive"))
      (node (ref "C20") (pin "2") (pinfunction "2_2") (pintype "passive"))
      (node (ref "C21") (pin "1") (pinfunction "1_1") (pintype "passive"))
      (node (ref "C22") (pin "1") (pinfunction "1_1") (pintype "passive"))
      (node (ref "C23") (pin "1") (pinfunction "1_1") (pintype "passive"))
      (node (ref "C24") (pin "1") (pinfunction "1_1") (pintype "passive"))
      (node (ref "C3") (pin "1") (pinfunction "1_1") (pintype "passive"))
      (node (ref "C4") (pin "1") (pinfunction "1_1") (pintype "passive"))
      (node (ref "C5") (pin "1") (pinfunction "1_1") (pintype "passive"))
      (node (ref "C6") (pin "1") (pinfunction "1_1") (pintype "passive"))
      (node (ref "C7") (pin "1") (pinfunction "1_1") (pintype "passive"))
      (node (ref "C8") (pin "1") (pinfunction "1_1") (pintype "passive"))
      (node (ref "C9") (pin "1") (pinfunction "1_1") (pintype "passive"))
      (node (ref "D1") (pin "2") (pinfunction "K_2") (pintype "passive"))
      (node (ref "J1") (pin "1") (pinfunction "GND_1") (pintype "passive"))
      (node (ref "P1") (pin "2") (pinfunction "2_2") (pintype "passive"))
      (node (ref "P11") (pin "2") (pinfunction "2_2") (pintype "passive"))
      (node (ref "P12") (pin "2") (pinfunction "2_2") (pintype "passive"))
      (node (ref "P15") (pin "2") (pinfunction "2_2") (pintype "passive"))
      (node (ref "P16") (pin "2") (pinfunction "2_2") (pintype "passive"))
      (node (ref "P2") (pin "2") (pinfunction "2_2") (pintype "passive"))
      (node (ref "P20") (pin "2") (pinfunction "2_2") (pintype "passive"))
      (node (ref "P21") (pin "2") (pinfunction "2_2") (pintype "passive"))
      (node (ref "P22") (pin "2") (pinfunction "2_2") (pintype "passive"))
      (node (ref "P23") (pin "2") (pinfunction "2_2") (pintype "passive"))
      (node (ref "P24") (pin "2") (pinfunction "2_2") (pintype "passive"))
      (node (ref "P25") (pin "2") (pinfunction "2_2") (pintype "passive"))
      (node (ref "P26") (pin "2") (pinfunction "2_2") (pintype "passive"))
      (node (ref "P3") (pin "2") (pinfunction "2_2") (pintype "passive"))
      (node (ref "P4") (pin "2") (pinfunction "2_2") (pintype "passive"))
      (node (ref "P5") (pin "2") (pinfunction "2_2") (pintype "passive"))
      (node (ref "P6") (pin "2") (pinfunction "2_2") (pintype "passive"))
      (node (ref "P8") (pin "2") (pinfunction "2_2") (pintype "passive"))
      (node (ref "S1") (pin "8") (pinfunction "GND_8") (pintype "passive"))
      (node (ref "S2") (pin "8") (pinfunction "GND_8") (pintype "passive"))
      (node (ref "S3") (pin "8") (pinfunction "GND_8") (pintype "passive"))
      (node (ref "S4") (pin "8") (pinfunction "GND_8") (pintype "passive"))
      (node (ref "S5") (pin "8") (pinfunction "GND_8") (pintype "passive"))
      (node (ref "S6") (pin "8") (pinfunction "GND_8") (pintype "passive"))
      (node (ref "S7") (pin "8") (pinfunction "GND_8") (pintype "passive"))
      (node (ref "SW1") (pin "2") (pinfunction "NO_2") (pintype "passive"))
      (node (ref "SW2") (pin "2") (pinfunction "NO_2") (pintype "passive"))
      (node (ref "U1") (pin "2") (pinfunction "GND_2") (pintype "passive"))
      (node (ref "U2") (pin "4") (pinfunction "GND_4") (pintype "passive"))
      (node (ref "U3") (pin "1") (pinfunction "GND_1") (pintype "passive"))
      (node (ref "U3") (pin "11") (pinfunction "P2_0_11") (pintype "passive"))
      (node (ref "U3") (pin "12") (pinfunction "P1_7_12") (pintype "passive"))
      (node (ref "U3") (pin "13") (pinfunction "P1_6_13") (pintype "passive"))
      (node (ref "U3") (pin "18") (pinfunction "GND_18") (pintype "passive"))
      (node (ref "U3") (pin "19") (pinfunction "P1_5_19") (pintype "passive"))
      (node (ref "U3") (pin "2") (pinfunction "GND_2") (pintype "passive"))
      (node (ref "U3") (pin "20") (pinfunction "P1_4_20") (pintype "passive"))
      (node (ref "U3") (pin "21") (pinfunction "P1_3_21") (pintype "passive"))
      (node (ref "U3") (pin "25") (pinfunction "GND_25") (pintype "passive"))
      (node (ref "U3") (pin "26") (pinfunction "P0_7_26") (pintype "passive"))
      (node (ref "U3") (pin "27") (pinfunction "P0_6_27") (pintype "passive"))
      (node (ref "U3") (pin "28") (pinfunction "P0_5_28") (pintype "passive"))
      (node (ref "U3") (pin "29") (pinfunction "P0_4_29") (pintype "passive"))
      (node (ref "U3") (pin "3") (pinfunction "GND_3") (pintype "passive"))
      (node (ref "U3") (pin "36") (pinfunction "GND_36") (pintype "passive"))
      (node (ref "U3") (pin "4") (pinfunction "GND_4") (pintype "passive"))
      (node (ref "U3") (pin "5") (pinfunction "GND_5") (pintype "passive"))
      (node (ref "U3") (pin "6") (pinfunction "GND_6") (pintype "passive"))
      (node (ref "U3") (pin "7") (pinfunction "GND_7") (pintype "passive"))
      (node (ref "U4") (pin "4") (pinfunction "GND_4") (pintype "passive"))
      (node (ref "U5") (pin "2") (pinfunction "GND_2") (pintype "passive"))
      (node (ref "U5") (pin "3") (pinfunction "GND_3") (pintype "passive"))
      (node (ref "U6") (pin "2") (pinfunction "GND_2") (pintype "passive"))
      (node (ref "U6") (pin "3") (pinfunction "GND_3") (pintype "passive"))
      (node (ref "U7") (pin "2") (pinfunction "GND_2") (pintype "passive"))
      (node (ref "U7") (pin "3") (pinfunction "GND_3") (pintype "passive"))
      (node (ref "U8") (pin "0") (pinfunction "GND_0") (pintype "passive"))
      (node (ref "U8") (pin "11") (pinfunction "4Y_11") (pintype "passive"))
      (node (ref "U8") (pin "12") (pinfunction "4A_12") (pintype "passive"))
      (node (ref "U8") (pin "13") (pinfunction "4~{OE}_13") (pintype "passive"))
      (node (ref "U8") (pin "7") (pinfunction "GND_7") (pintype "passive"))
      (node (ref "U9") (pin "2") (pinfunction "GND_2") (pintype "passive"))
      (node (ref "U9") (pin "3") (pinfunction "GND_3") (pintype "passive"))
    )
    (net (code "18") (name "Net-(BAT1--)") (class "Default")
      (node (ref "BAT1") (pin "2") (pinfunction "-_2") (pintype "passive"))
      (node (ref "BAT2") (pin "1") (pinfunction "+_1") (pintype "passive"))
    )
    (net (code "19") (name "Net-(BAT2--)") (class "Default")
      (node (ref "BAT2") (pin "2") (pinfunction "-_2") (pintype "passive"))
      (node (ref "SW1") (pin "1") (pinfunction "COMMON_1") (pintype "passive"))
    )
    (net (code "20") (name "Net-(BAT3--)") (class "Default")
      (node (ref "BAT3") (pin "2") (pinfunction "-_2") (pintype "passive"))
      (node (ref "SW2") (pin "1") (pinfunction "COMMON_1") (pintype "passive"))
    )
    (net (code "21") (name "Net-(D1-A)") (class "Default")
      (node (ref "D1") (pin "1") (pinfunction "A_1") (pintype "passive"))
      (node (ref "R7") (pin "1") (pinfunction "1_1") (pintype "passive"))
    )
    (net (code "22") (name "Net-(S1-LEDA)") (class "Default")
      (node (ref "C6") (pin "2") (pinfunction "2_2") (pintype "passive"))
      (node (ref "R1") (pin "1") (pinfunction "1_1") (pintype "passive"))
      (node (ref "S1") (pin "10") (pinfunction "LEDA_10") (pintype "passive"))
    )
    (net (code "23") (name "Net-(S2-LEDA)") (class "Default")
      (node (ref "C7") (pin "2") (pinfunction "2_2") (pintype "passive"))
      (node (ref "R2") (pin "1") (pinfunction "1_1") (pintype "passive"))
      (node (ref "S2") (pin "10") (pinfunction "LEDA_10") (pintype "passive"))
    )
    (net (code "24") (name "Net-(S3-LEDA)") (class "Default")
      (node (ref "C12") (pin "2") (pinfunction "2_2") (pintype "passive"))
      (node (ref "R5") (pin "1") (pinfunction "1_1") (pintype "passive"))
      (node (ref "S3") (pin "10") (pinfunction "LEDA_10") (pintype "passive"))
    )
    (net (code "25") (name "Net-(S4-LEDA)") (class "Default")
      (node (ref "C13") (pin "2") (pinfunction "2_2") (pintype "passive"))
      (node (ref "R6") (pin "1") (pinfunction "1_1") (pintype "passive"))
      (node (ref "S4") (pin "10") (pinfunction "LEDA_10") (pintype "passive"))
    )
    (net (code "26") (name "Net-(S5-LEDA)") (class "Default")
      (node (ref "C21") (pin "2") (pinfunction "2_2") (pintype "passive"))
      (node (ref "R8") (pin "1") (pinfunction "1_1") (pintype "passive"))
      (node (ref "S5") (pin "10") (pinfunction "LEDA_10") (pintype "passive"))
    )
    (net (code "27") (name "Net-(S6-LEDA)") (class "Default")
      (node (ref "C22") (pin "2") (pinfunction "2_2") (pintype "passive"))
      (node (ref "R9") (pin "1") (pinfunction "1_1") (pintype "passive"))
      (node (ref "S6") (pin "10") (pinfunction "LEDA_10") (pintype "passive"))
    )
    (net (code "28") (name "Net-(S7-LEDA)") (class "Default")
      (node (ref "C23") (pin "2") (pinfunction "2_2") (pintype "passive"))
      (node (ref "R10") (pin "1") (pinfunction "1_1") (pintype "passive"))
      (node (ref "S7") (pin "10") (pinfunction "LEDA_10") (pintype "passive"))
    )
    (net (code "29") (name "Net-(U1-SW)") (class "Default")
      (node (ref "L1") (pin "1") (pinfunction "1_1") (pintype "passive"))
      (node (ref "U1") (pin "5") (pinfunction "SW_5") (pintype "passive"))
    )
    (net (code "30") (name "VBAT") (class "Default")
      (node (ref "BAT1") (pin "1") (pinfunction "+_1") (pintype "passive"))
      (node (ref "BAT3") (pin "1") (pinfunction "+_1") (pintype "passive"))
      (node (ref "C1") (pin "1") (pinfunction "1_1") (pintype "passive"))
      (node (ref "C2") (pin "2") (pinfunction "2_2") (pintype "passive"))
      (node (ref "P1") (pin "1") (pinfunction "1_1") (pintype "passive"))
      (node (ref "P2") (pin "1") (pinfunction "1_1") (pintype "passive"))
      (node (ref "P3") (pin "1") (pinfunction "1_1") (pintype "passive"))
      (node (ref "R7") (pin "2") (pinfunction "2_2") (pintype "passive"))
      (node (ref "U1") (pin "1") (pinfunction "VIN_1") (pintype "passive"))
      (node (ref "U1") (pin "3") (pinfunction "CE_3") (pintype "passive"))
    )
    (net (code "31") (name "unconnected-(J1-+3V3_(DE)-Pad9)") (class "Default")
      (node (ref "J1") (pin "9") (pinfunction "+3V3_(DE)_9") (pintype "passive+no_connect"))
    )
    (net (code "32") (name "unconnected-(J1-CSn-Pad5)") (class "Default")
      (node (ref "J1") (pin "5") (pinfunction "CSn_5") (pintype "passive+no_connect"))
    )
    (net (code "33") (name "unconnected-(J1-MISO-Pad10)") (class "Default")
      (node (ref "J1") (pin "10") (pinfunction "MISO_10") (pintype "passive+no_connect"))
    )
    (net (code "34") (name "unconnected-(J1-MOSI-Pad8)") (class "Default")
      (node (ref "J1") (pin "8") (pinfunction "MOSI_8") (pintype "passive+no_connect"))
    )
    (net (code "35") (name "unconnected-(J1-SCLK-Pad6)") (class "Default")
      (node (ref "J1") (pin "6") (pinfunction "SCLK_6") (pintype "passive+no_connect"))
    )
    (net (code "36") (name "unconnected-(S1-DNC-Pad1)") (class "Default")
      (node (ref "S1") (pin "1") (pinfunction "DNC_1") (pintype "passive+no_connect"))
    )
    (net (code "37") (name "unconnected-(S1-INT-Pad5)") (class "Default")
      (node (ref "S1") (pin "5") (pinfunction "INT_5") (pintype "passive+no_connect"))
    )
    (net (code "38") (name "unconnected-(S1-LED1-Pad9)") (class "Default")
      (node (ref "S1") (pin "9") (pinfunction "LED1_9") (pintype "passive+no_connect"))
    )
    (net (code "39") (name "unconnected-(S2-DNC-Pad1)") (class "Default")
      (node (ref "S2") (pin "1") (pinfunction "DNC_1") (pintype "passive+no_connect"))
    )
    (net (code "40") (name "unconnected-(S2-INT-Pad5)") (class "Default")
      (node (ref "S2") (pin "5") (pinfunction "INT_5") (pintype "passive+no_connect"))
    )
    (net (code "41") (name "unconnected-(S2-LED1-Pad9)") (class "Default")
      (node (ref "S2") (pin "9") (pinfunction "LED1_9") (pintype "passive+no_connect"))
    )
    (net (code "42") (name "unconnected-(S3-DNC-Pad1)") (class "Default")
      (node (ref "S3") (pin "1") (pinfunction "DNC_1") (pintype "passive+no_connect"))
    )
    (net (code "43") (name "unconnected-(S3-INT-Pad5)") (class "Default")
      (node (ref "S3") (pin "5") (pinfunction "INT_5") (pintype "passive+no_connect"))
    )
    (net (code "44") (name "unconnected-(S3-LED1-Pad9)") (class "Default")
      (node (ref "S3") (pin "9") (pinfunction "LED1_9") (pintype "passive+no_connect"))
    )
    (net (code "45") (name "unconnected-(S4-DNC-Pad1)") (class "Default")
      (node (ref "S4") (pin "1") (pinfunction "DNC_1") (pintype "passive+no_connect"))
    )
    (net (code "46") (name "unconnected-(S4-INT-Pad5)") (class "Default")
      (node (ref "S4") (pin "5") (pinfunction "INT_5") (pintype "passive+no_connect"))
    )
    (net (code "47") (name "unconnected-(S4-LED1-Pad9)") (class "Default")
      (node (ref "S4") (pin "9") (pinfunction "LED1_9") (pintype "passive+no_connect"))
    )
    (net (code "48") (name "unconnected-(S5-DNC-Pad1)") (class "Default")
      (node (ref "S5") (pin "1") (pinfunction "DNC_1") (pintype "passive+no_connect"))
    )
    (net (code "49") (name "unconnected-(S5-INT-Pad5)") (class "Default")
      (node (ref "S5") (pin "5") (pinfunction "INT_5") (pintype "passive+no_connect"))
    )
    (net (code "50") (name "unconnected-(S5-LED1-Pad9)") (class "Default")
      (node (ref "S5") (pin "9") (pinfunction "LED1_9") (pintype "passive+no_connect"))
    )
    (net (code "51") (name "unconnected-(S6-DNC-Pad1)") (class "Default")
      (node (ref "S6") (pin "1") (pinfunction "DNC_1") (pintype "passive+no_connect"))
    )
    (net (code "52") (name "unconnected-(S6-INT-Pad5)") (class "Default")
      (node (ref "S6") (pin "5") (pinfunction "INT_5") (pintype "passive+no_connect"))
    )
    (net (code "53") (name "unconnected-(S6-LED1-Pad9)") (class "Default")
      (node (ref "S6") (pin "9") (pinfunction "LED1_9") (pintype "passive+no_connect"))
    )
    (net (code "54") (name "unconnected-(S7-DNC-Pad1)") (class "Default")
      (node (ref "S7") (pin "1") (pinfunction "DNC_1") (pintype "passive+no_connect"))
    )
    (net (code "55") (name "unconnected-(S7-INT-Pad5)") (class "Default")
      (node (ref "S7") (pin "5") (pinfunction "INT_5") (pintype "passive+no_connect"))
    )
    (net (code "56") (name "unconnected-(S7-LED1-Pad9)") (class "Default")
      (node (ref "S7") (pin "9") (pinfunction "LED1_9") (pintype "passive+no_connect"))
    )
    (net (code "57") (name "unconnected-(U3-NC-Pad16)") (class "Default")
      (node (ref "U3") (pin "16") (pinfunction "NC_16") (pintype "passive+no_connect"))
    )
    (net (code "58") (name "unconnected-(U3-NC-Pad35)") (class "Default")
      (node (ref "U3") (pin "35") (pinfunction "NC_35") (pintype "passive+no_connect"))
    )
  )
)
